# rc-tx-board-V1.net
KiCad netlist of a schematic drawn in EAGLE
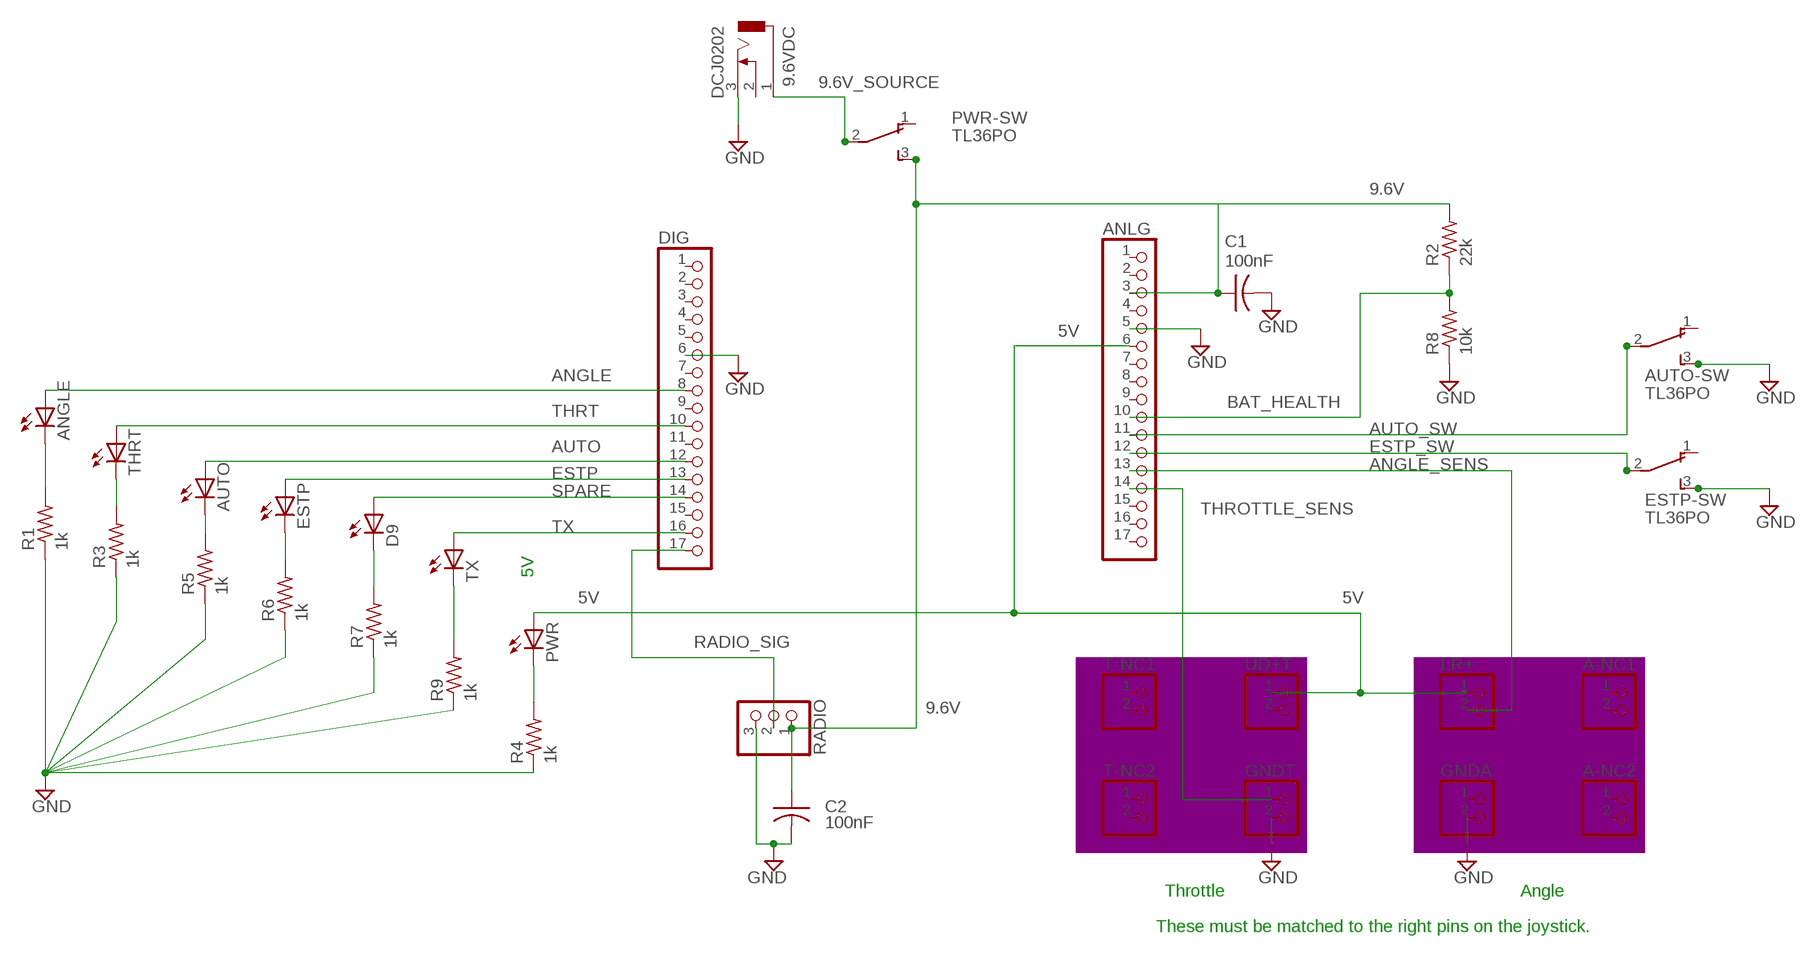
[diagram p0: schematic, sheet 1]

(export (version "E")
  (design (tool "Eeschema 10.0.6"))
  (components
    (comp (ref "9.6VDC")
      (value "DCJ0202")
      (footprint "eagle-import:DCJ0202")
      (libsource (lib "eagle-import") (part "DCJ0202"))
    )
    (comp (ref "A-NC1")
      (value "PINHD-1X2")
      (footprint "eagle-import:1X02")
      (libsource (lib "eagle-import") (part "PINHD-1X2"))
    )
    (comp (ref "A-NC2")
      (value "PINHD-1X2")
      (footprint "eagle-import:1X02")
      (libsource (lib "eagle-import") (part "PINHD-1X2"))
    )
    (comp (ref "ANGLE")
      (value "LED5MM")
      (footprint "eagle-import:LED5MM")
      (libsource (lib "eagle-import") (part "LED5MM"))
    )
    (comp (ref "ANLG")
      (value "PINHD-1X17")
      (footprint "eagle-import:1X17")
      (libsource (lib "eagle-import") (part "PINHD-1X17"))
    )
    (comp (ref "AUTO")
      (value "LED5MM")
      (footprint "eagle-import:LED5MM")
      (libsource (lib "eagle-import") (part "LED5MM"))
    )
    (comp (ref "AUTO-SW")
      (value "TL36PO")
      (footprint "eagle-import:TL3XPO")
      (libsource (lib "eagle-import") (part "TL36PO"))
    )
    (comp (ref "C1")
      (value "100nF")
      (footprint "eagle-import:C050-024X044")
      (libsource (lib "eagle-import") (part "C-US050-024X044"))
    )
    (comp (ref "C2")
      (value "100nF")
      (footprint "eagle-import:C050-024X044")
      (libsource (lib "eagle-import") (part "C-US050-024X044"))
    )
    (comp (ref "D9")
      (value "LED5MM")
      (footprint "eagle-import:LED5MM")
      (libsource (lib "eagle-import") (part "LED5MM"))
    )
    (comp (ref "DIG")
      (value "PINHD-1X17")
      (footprint "eagle-import:1X17")
      (libsource (lib "eagle-import") (part "PINHD-1X17"))
    )
    (comp (ref "ESTP")
      (value "LED5MM")
      (footprint "eagle-import:LED5MM")
      (libsource (lib "eagle-import") (part "LED5MM"))
    )
    (comp (ref "ESTP-SW")
      (value "TL36PO")
      (footprint "eagle-import:TL3XPO")
      (libsource (lib "eagle-import") (part "TL36PO"))
    )
    (comp (ref "GNDA")
      (value "PINHD-1X2")
      (footprint "eagle-import:1X02")
      (libsource (lib "eagle-import") (part "PINHD-1X2"))
    )
    (comp (ref "GNDT")
      (value "PINHD-1X2")
      (footprint "eagle-import:1X02")
      (libsource (lib "eagle-import") (part "PINHD-1X2"))
    )
    (comp (ref "LR+")
      (value "PINHD-1X2")
      (footprint "eagle-import:1X02")
      (libsource (lib "eagle-import") (part "PINHD-1X2"))
    )
    (comp (ref "PWR")
      (value "LED5MM")
      (footprint "eagle-import:LED5MM")
      (libsource (lib "eagle-import") (part "LED5MM"))
    )
    (comp (ref "PWR-SW")
      (value "TL36PO")
      (footprint "eagle-import:TL3XPO")
      (libsource (lib "eagle-import") (part "TL36PO"))
    )
    (comp (ref "R1")
      (value "1k")
      (footprint "eagle-import:0207_10")
      (libsource (lib "eagle-import") (part "R-US_0207/10"))
    )
    (comp (ref "R2")
      (value "22k")
      (footprint "eagle-import:0207_10")
      (libsource (lib "eagle-import") (part "R-US_0207/10"))
    )
    (comp (ref "R3")
      (value "1k")
      (footprint "eagle-import:0207_10")
      (libsource (lib "eagle-import") (part "R-US_0207/10"))
    )
    (comp (ref "R4")
      (value "1k")
      (footprint "eagle-import:0207_10")
      (libsource (lib "eagle-import") (part "R-US_0207/10"))
    )
    (comp (ref "R5")
      (value "1k")
      (footprint "eagle-import:0207_10")
      (libsource (lib "eagle-import") (part "R-US_0207/10"))
    )
    (comp (ref "R6")
      (value "1k")
      (footprint "eagle-import:0207_10")
      (libsource (lib "eagle-import") (part "R-US_0207/10"))
    )
    (comp (ref "R7")
      (value "1k")
      (footprint "eagle-import:0207_10")
      (libsource (lib "eagle-import") (part "R-US_0207/10"))
    )
    (comp (ref "R8")
      (value "10k")
      (footprint "eagle-import:0207_10")
      (libsource (lib "eagle-import") (part "R-US_0207/10"))
    )
    (comp (ref "R9")
      (value "1k")
      (footprint "eagle-import:0207_10")
      (libsource (lib "eagle-import") (part "R-US_0207/10"))
    )
    (comp (ref "RADIO")
      (value "PINHD-1X3")
      (footprint "eagle-import:1X03")
      (libsource (lib "eagle-import") (part "PINHD-1X3"))
    )
    (comp (ref "T-NC1")
      (value "PINHD-1X2")
      (footprint "eagle-import:1X02")
      (libsource (lib "eagle-import") (part "PINHD-1X2"))
    )
    (comp (ref "T-NC2")
      (value "PINHD-1X2")
      (footprint "eagle-import:1X02")
      (libsource (lib "eagle-import") (part "PINHD-1X2"))
    )
    (comp (ref "THRT")
      (value "LED5MM")
      (footprint "eagle-import:LED5MM")
      (libsource (lib "eagle-import") (part "LED5MM"))
    )
    (comp (ref "TX")
      (value "LED5MM")
      (footprint "eagle-import:LED5MM")
      (libsource (lib "eagle-import") (part "LED5MM"))
    )
    (comp (ref "UD+T")
      (value "PINHD-1X2")
      (footprint "eagle-import:1X02")
      (libsource (lib "eagle-import") (part "PINHD-1X2"))
    )
  )
  (nets
    (net (code "1") (name "5V") (class "Default")
      (node (ref "ANLG") (pin "6") (pinfunction "6_6") (pintype "passive"))
      (node (ref "LR+") (pin "1") (pinfunction "1_1") (pintype "passive"))
      (node (ref "PWR") (pin "A") (pinfunction "A_A") (pintype "passive"))
      (node (ref "UD+T") (pin "1") (pinfunction "1_1") (pintype "passive"))
    )
    (net (code "2") (name "9.6V") (class "Default")
      (node (ref "ANLG") (pin "3") (pinfunction "3_3") (pintype "passive"))
      (node (ref "C1") (pin "1") (pinfunction "1_1") (pintype "passive"))
      (node (ref "C2") (pin "1") (pinfunction "1_1") (pintype "passive"))
      (node (ref "PWR-SW") (pin "3") (pinfunction "S_3") (pintype "passive"))
      (node (ref "R2") (pin "2") (pinfunction "2_2") (pintype "passive"))
      (node (ref "RADIO") (pin "1") (pinfunction "1_1") (pintype "passive"))
    )
    (net (code "3") (name "9.6V_SOURCE") (class "Default")
      (node (ref "9.6VDC") (pin "1") (pinfunction "1_1") (pintype "passive"))
      (node (ref "PWR-SW") (pin "2") (pinfunction "P_2") (pintype "passive"))
    )
    (net (code "4") (name "ANGLE") (class "Default")
      (node (ref "ANGLE") (pin "A") (pinfunction "A_A") (pintype "passive"))
      (node (ref "DIG") (pin "8") (pinfunction "8_8") (pintype "passive"))
    )
    (net (code "5") (name "ANGLE_SENS") (class "Default")
      (node (ref "ANLG") (pin "13") (pinfunction "13_13") (pintype "passive"))
      (node (ref "LR+") (pin "2") (pinfunction "2_2") (pintype "passive"))
    )
    (net (code "6") (name "AUTO") (class "Default")
      (node (ref "AUTO") (pin "A") (pinfunction "A_A") (pintype "passive"))
      (node (ref "DIG") (pin "12") (pinfunction "12_12") (pintype "passive"))
    )
    (net (code "7") (name "AUTO_SW") (class "Default")
      (node (ref "ANLG") (pin "11") (pinfunction "11_11") (pintype "passive"))
      (node (ref "AUTO-SW") (pin "2") (pinfunction "P_2") (pintype "passive"))
    )
    (net (code "8") (name "BAT_HEALTH") (class "Default")
      (node (ref "ANLG") (pin "10") (pinfunction "10_10") (pintype "passive"))
      (node (ref "R2") (pin "1") (pinfunction "1_1") (pintype "passive"))
      (node (ref "R8") (pin "2") (pinfunction "2_2") (pintype "passive"))
    )
    (net (code "9") (name "ESTP") (class "Default")
      (node (ref "DIG") (pin "13") (pinfunction "13_13") (pintype "passive"))
      (node (ref "ESTP") (pin "A") (pinfunction "A_A") (pintype "passive"))
    )
    (net (code "10") (name "ESTP_SW") (class "Default")
      (node (ref "ANLG") (pin "12") (pinfunction "12_12") (pintype "passive"))
      (node (ref "ESTP-SW") (pin "2") (pinfunction "P_2") (pintype "passive"))
    )
    (net (code "11") (name "GND") (class "Default")
      (node (ref "9.6VDC") (pin "3") (pinfunction "3_3") (pintype "passive"))
      (node (ref "ANLG") (pin "5") (pinfunction "5_5") (pintype "passive"))
      (node (ref "AUTO-SW") (pin "3") (pinfunction "S_3") (pintype "passive"))
      (node (ref "C1") (pin "2") (pinfunction "2_2") (pintype "passive"))
      (node (ref "C2") (pin "2") (pinfunction "2_2") (pintype "passive"))
      (node (ref "DIG") (pin "6") (pinfunction "6_6") (pintype "passive"))
      (node (ref "ESTP-SW") (pin "3") (pinfunction "S_3") (pintype "passive"))
      (node (ref "GNDA") (pin "2") (pinfunction "2_2") (pintype "passive"))
      (node (ref "GNDT") (pin "2") (pinfunction "2_2") (pintype "passive"))
      (node (ref "R1") (pin "1") (pinfunction "1_1") (pintype "passive"))
      (node (ref "R3") (pin "1") (pinfunction "1_1") (pintype "passive"))
      (node (ref "R4") (pin "1") (pinfunction "1_1") (pintype "passive"))
      (node (ref "R5") (pin "1") (pinfunction "1_1") (pintype "passive"))
      (node (ref "R6") (pin "1") (pinfunction "1_1") (pintype "passive"))
      (node (ref "R7") (pin "1") (pinfunction "1_1") (pintype "passive"))
      (node (ref "R8") (pin "1") (pinfunction "1_1") (pintype "passive"))
      (node (ref "R9") (pin "1") (pinfunction "1_1") (pintype "passive"))
      (node (ref "RADIO") (pin "3") (pinfunction "3_3") (pintype "passive"))
    )
    (net (code "12") (name "Net-(ANGLE-C)") (class "Default")
      (node (ref "ANGLE") (pin "K") (pinfunction "C_K") (pintype "passive"))
      (node (ref "R1") (pin "2") (pinfunction "2_2") (pintype "passive"))
    )
    (net (code "13") (name "Net-(AUTO-C)") (class "Default")
      (node (ref "AUTO") (pin "K") (pinfunction "C_K") (pintype "passive"))
      (node (ref "R5") (pin "2") (pinfunction "2_2") (pintype "passive"))
    )
    (net (code "14") (name "Net-(D9-C)") (class "Default")
      (node (ref "D9") (pin "K") (pinfunction "C_K") (pintype "passive"))
      (node (ref "R7") (pin "2") (pinfunction "2_2") (pintype "passive"))
    )
    (net (code "15") (name "Net-(ESTP-C)") (class "Default")
      (node (ref "ESTP") (pin "K") (pinfunction "C_K") (pintype "passive"))
      (node (ref "R6") (pin "2") (pinfunction "2_2") (pintype "passive"))
    )
    (net (code "16") (name "Net-(PWR-C)") (class "Default")
      (node (ref "PWR") (pin "K") (pinfunction "C_K") (pintype "passive"))
      (node (ref "R4") (pin "2") (pinfunction "2_2") (pintype "passive"))
    )
    (net (code "17") (name "Net-(THRT-C)") (class "Default")
      (node (ref "R3") (pin "2") (pinfunction "2_2") (pintype "passive"))
      (node (ref "THRT") (pin "K") (pinfunction "C_K") (pintype "passive"))
    )
    (net (code "18") (name "Net-(TX-C)") (class "Default")
      (node (ref "R9") (pin "2") (pinfunction "2_2") (pintype "passive"))
      (node (ref "TX") (pin "K") (pinfunction "C_K") (pintype "passive"))
    )
    (net (code "19") (name "RADIO_SIG") (class "Default")
      (node (ref "DIG") (pin "17") (pinfunction "17_17") (pintype "passive"))
      (node (ref "RADIO") (pin "2") (pinfunction "2_2") (pintype "passive"))
    )
    (net (code "20") (name "SPARE") (class "Default")
      (node (ref "D9") (pin "A") (pinfunction "A_A") (pintype "passive"))
      (node (ref "DIG") (pin "14") (pinfunction "14_14") (pintype "passive"))
    )
    (net (code "21") (name "THROTTLE_SENS") (class "Default")
      (node (ref "ANLG") (pin "14") (pinfunction "14_14") (pintype "passive"))
      (node (ref "GNDT") (pin "1") (pinfunction "1_1") (pintype "passive"))
    )
    (net (code "22") (name "THRT") (class "Default")
      (node (ref "DIG") (pin "10") (pinfunction "10_10") (pintype "passive"))
      (node (ref "THRT") (pin "A") (pinfunction "A_A") (pintype "passive"))
    )
    (net (code "23") (name "TX") (class "Default")
      (node (ref "DIG") (pin "16") (pinfunction "16_16") (pintype "passive"))
      (node (ref "TX") (pin "A") (pinfunction "A_A") (pintype "passive"))
    )
    (net (code "24") (name "unconnected-(9.6VDC-Pad2)") (class "Default")
      (node (ref "9.6VDC") (pin "2") (pinfunction "2_2") (pintype "passive"))
    )
    (net (code "25") (name "unconnected-(A-NC1-Pad1)") (class "Default")
      (node (ref "A-NC1") (pin "1") (pinfunction "1_1") (pintype "passive"))
    )
    (net (code "26") (name "unconnected-(A-NC1-Pad2)") (class "Default")
      (node (ref "A-NC1") (pin "2") (pinfunction "2_2") (pintype "passive"))
    )
    (net (code "27") (name "unconnected-(A-NC2-Pad1)") (class "Default")
      (node (ref "A-NC2") (pin "1") (pinfunction "1_1") (pintype "passive"))
    )
    (net (code "28") (name "unconnected-(A-NC2-Pad2)") (class "Default")
      (node (ref "A-NC2") (pin "2") (pinfunction "2_2") (pintype "passive"))
    )
    (net (code "29") (name "unconnected-(ANLG-Pad1)") (class "Default")
      (node (ref "ANLG") (pin "1") (pinfunction "1_1") (pintype "passive"))
    )
    (net (code "30") (name "unconnected-(ANLG-Pad2)") (class "Default")
      (node (ref "ANLG") (pin "2") (pinfunction "2_2") (pintype "passive"))
    )
    (net (code "31") (name "unconnected-(ANLG-Pad4)") (class "Default")
      (node (ref "ANLG") (pin "4") (pinfunction "4_4") (pintype "passive"))
    )
    (net (code "32") (name "unconnected-(ANLG-Pad7)") (class "Default")
      (node (ref "ANLG") (pin "7") (pinfunction "7_7") (pintype "passive"))
    )
    (net (code "33") (name "unconnected-(ANLG-Pad8)") (class "Default")
      (node (ref "ANLG") (pin "8") (pinfunction "8_8") (pintype "passive"))
    )
    (net (code "34") (name "unconnected-(ANLG-Pad9)") (class "Default")
      (node (ref "ANLG") (pin "9") (pinfunction "9_9") (pintype "passive"))
    )
    (net (code "35") (name "unconnected-(ANLG-Pad15)") (class "Default")
      (node (ref "ANLG") (pin "15") (pinfunction "15_15") (pintype "passive"))
    )
    (net (code "36") (name "unconnected-(ANLG-Pad16)") (class "Default")
      (node (ref "ANLG") (pin "16") (pinfunction "16_16") (pintype "passive"))
    )
    (net (code "37") (name "unconnected-(ANLG-Pad17)") (class "Default")
      (node (ref "ANLG") (pin "17") (pinfunction "17_17") (pintype "passive"))
    )
    (net (code "38") (name "unconnected-(AUTO-SW-O-Pad1)") (class "Default")
      (node (ref "AUTO-SW") (pin "1") (pinfunction "O_1") (pintype "passive"))
    )
    (net (code "39") (name "unconnected-(DIG-Pad1)") (class "Default")
      (node (ref "DIG") (pin "1") (pinfunction "1_1") (pintype "passive"))
    )
    (net (code "40") (name "unconnected-(DIG-Pad2)") (class "Default")
      (node (ref "DIG") (pin "2") (pinfunction "2_2") (pintype "passive"))
    )
    (net (code "41") (name "unconnected-(DIG-Pad3)") (class "Default")
      (node (ref "DIG") (pin "3") (pinfunction "3_3") (pintype "passive"))
    )
    (net (code "42") (name "unconnected-(DIG-Pad4)") (class "Default")
      (node (ref "DIG") (pin "4") (pinfunction "4_4") (pintype "passive"))
    )
    (net (code "43") (name "unconnected-(DIG-Pad5)") (class "Default")
      (node (ref "DIG") (pin "5") (pinfunction "5_5") (pintype "passive"))
    )
    (net (code "44") (name "unconnected-(DIG-Pad7)") (class "Default")
      (node (ref "DIG") (pin "7") (pinfunction "7_7") (pintype "passive"))
    )
    (net (code "45") (name "unconnected-(DIG-Pad9)") (class "Default")
      (node (ref "DIG") (pin "9") (pinfunction "9_9") (pintype "passive"))
    )
    (net (code "46") (name "unconnected-(DIG-Pad11)") (class "Default")
      (node (ref "DIG") (pin "11") (pinfunction "11_11") (pintype "passive"))
    )
    (net (code "47") (name "unconnected-(DIG-Pad15)") (class "Default")
      (node (ref "DIG") (pin "15") (pinfunction "15_15") (pintype "passive"))
    )
    (net (code "48") (name "unconnected-(ESTP-SW-O-Pad1)") (class "Default")
      (node (ref "ESTP-SW") (pin "1") (pinfunction "O_1") (pintype "passive"))
    )
    (net (code "49") (name "unconnected-(GNDA-Pad1)") (class "Default")
      (node (ref "GNDA") (pin "1") (pinfunction "1_1") (pintype "passive"))
    )
    (net (code "50") (name "unconnected-(PWR-SW-O-Pad1)") (class "Default")
      (node (ref "PWR-SW") (pin "1") (pinfunction "O_1") (pintype "passive"))
    )
    (net (code "51") (name "unconnected-(T-NC1-Pad1)") (class "Default")
      (node (ref "T-NC1") (pin "1") (pinfunction "1_1") (pintype "passive"))
    )
    (net (code "52") (name "unconnected-(T-NC1-Pad2)") (class "Default")
      (node (ref "T-NC1") (pin "2") (pinfunction "2_2") (pintype "passive"))
    )
    (net (code "53") (name "unconnected-(T-NC2-Pad1)") (class "Default")
      (node (ref "T-NC2") (pin "1") (pinfunction "1_1") (pintype "passive"))
    )
    (net (code "54") (name "unconnected-(T-NC2-Pad2)") (class "Default")
      (node (ref "T-NC2") (pin "2") (pinfunction "2_2") (pintype "passive"))
    )
    (net (code "55") (name "unconnected-(UD+T-Pad2)") (class "Default")
      (node (ref "UD+T") (pin "2") (pinfunction "2_2") (pintype "passive"))
    )
  )
)
